# motor_drive.net
KiCad netlist of a schematic drawn in Altium Designer
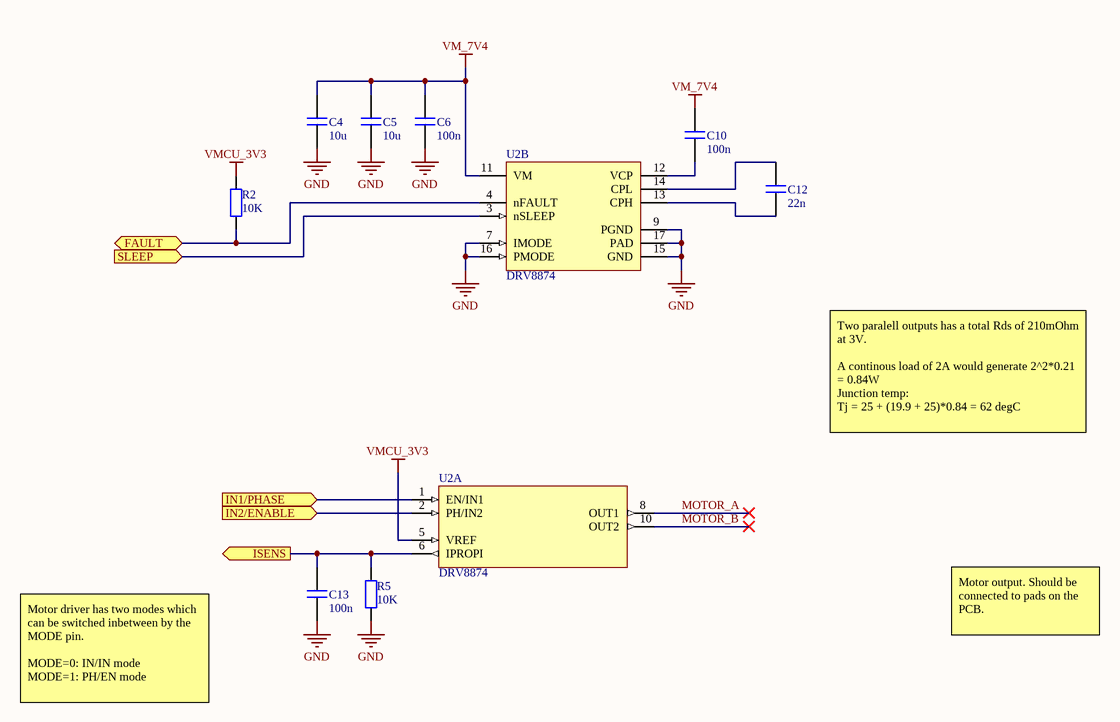
[diagram p0: motor_drive.SchDoc]

(export (version "E")
  (design (tool "Eeschema 10.0.6"))
  (components
    (comp (ref "C4")
      (value "10u")
      (footprint "CAPC3216X14N")
      (description "Capacitor")
      (fields (field (name "Comment") "cap"))
      (libsource (lib "lib_passives") (part "cap"))
    )
    (comp (ref "C5")
      (value "10u")
      (footprint "CAPC3216X14N")
      (description "Capacitor")
      (fields (field (name "Comment") "cap"))
      (libsource (lib "lib_passives") (part "cap"))
    )
    (comp (ref "C6")
      (value "100n")
      (footprint "CAPC1005X06N")
      (description "Capacitor")
      (fields (field (name "Comment") "cap"))
      (libsource (lib "lib_passives") (part "cap"))
    )
    (comp (ref "C10")
      (value "100n")
      (footprint "CAPC1005X06N")
      (description "Capacitor")
      (fields (field (name "Comment") "cap"))
      (libsource (lib "lib_passives") (part "cap"))
    )
    (comp (ref "C12")
      (value "22n")
      (footprint "CAPC1005X06N")
      (description "Capacitor")
      (fields (field (name "Comment") "cap"))
      (libsource (lib "lib_passives") (part "cap"))
    )
    (comp (ref "C13")
      (value "100n")
      (footprint "CAPC1005X06N")
      (description "Capacitor")
      (fields (field (name "Comment") "cap"))
      (libsource (lib "lib_passives") (part "cap"))
    )
    (comp (ref "R2")
      (value "10K")
      (footprint "RESC1005X04N")
      (description "Resistor")
      (fields (field (name "Comment") "res"))
      (libsource (lib "lib_passives") (part "res"))
    )
    (comp (ref "R5")
      (value "10K")
      (footprint "RESC1005X04N")
      (description "Resistor")
      (fields (field (name "Comment") "res"))
      (libsource (lib "lib_passives") (part "res"))
    )
    (comp (ref "U2")
      (value "DRV8874")
      (footprint "TSOP65P640X120_HS-17N_DRV8874")
      (description "H-Bridge Motor Driver With Integrated Current Sense and Regulation")
      (libsource (lib "lib_ti") (part "drv8874"))
    )
  )
  (nets
    (net (code "1") (name "/FAULT") (class "Default")
      (node (ref "R2") (pin "1") (pinfunction "1_1") (pintype "passive"))
      (node (ref "U2") (pin "4") (pinfunction "nFAULT_4") (pintype "open_collector"))
    )
    (net (code "2") (name "/IN1{slash}PHASE") (class "Default")
      (node (ref "U2") (pin "1") (pinfunction "EN/IN1_1") (pintype "input"))
    )
    (net (code "3") (name "/IN2{slash}ENABLE") (class "Default")
      (node (ref "U2") (pin "2") (pinfunction "PH/IN2_2") (pintype "input"))
    )
    (net (code "4") (name "/ISENS") (class "Default")
      (node (ref "C13") (pin "2") (pinfunction "2_2") (pintype "passive"))
      (node (ref "R5") (pin "2") (pinfunction "2_2") (pintype "passive"))
      (node (ref "U2") (pin "6") (pinfunction "IPROPI_6") (pintype "output"))
    )
    (net (code "5") (name "/MOTOR_A") (class "Default")
      (node (ref "U2") (pin "8") (pinfunction "OUT1_8") (pintype "output+no_connect"))
    )
    (net (code "6") (name "/MOTOR_B") (class "Default")
      (node (ref "U2") (pin "10") (pinfunction "OUT2_10") (pintype "output+no_connect"))
    )
    (net (code "7") (name "/SLEEP") (class "Default")
      (node (ref "U2") (pin "3") (pinfunction "nSLEEP_3") (pintype "input"))
    )
    (net (code "8") (name "GND") (class "Default")
      (node (ref "C13") (pin "1") (pinfunction "1_1") (pintype "passive"))
      (node (ref "C4") (pin "1") (pinfunction "1_1") (pintype "passive"))
      (node (ref "C5") (pin "1") (pinfunction "1_1") (pintype "passive"))
      (node (ref "C6") (pin "1") (pinfunction "1_1") (pintype "passive"))
      (node (ref "R5") (pin "1") (pinfunction "1_1") (pintype "passive"))
      (node (ref "U2") (pin "15") (pinfunction "GND_15") (pintype "power_in"))
      (node (ref "U2") (pin "16") (pinfunction "PMODE_16") (pintype "input"))
      (node (ref "U2") (pin "17") (pinfunction "PAD_17") (pintype "power_in"))
      (node (ref "U2") (pin "7") (pinfunction "IMODE_7") (pintype "input"))
      (node (ref "U2") (pin "9") (pinfunction "PGND_9") (pintype "power_in"))
    )
    (net (code "9") (name "Net-(U2B-CPH)") (class "Default")
      (node (ref "C12") (pin "1") (pinfunction "1_1") (pintype "passive"))
      (node (ref "U2") (pin "13") (pinfunction "CPH_13") (pintype "passive"))
    )
    (net (code "10") (name "Net-(U2B-CPL)") (class "Default")
      (node (ref "C12") (pin "2") (pinfunction "2_2") (pintype "passive"))
      (node (ref "U2") (pin "14") (pinfunction "CPL_14") (pintype "passive"))
    )
    (net (code "11") (name "Net-(U2B-VCP)") (class "Default")
      (node (ref "C10") (pin "1") (pinfunction "1_1") (pintype "passive"))
      (node (ref "U2") (pin "12") (pinfunction "VCP_12") (pintype "power_in"))
    )
    (net (code "12") (name "VMCU_3V3") (class "Default")
      (node (ref "R2") (pin "2") (pinfunction "2_2") (pintype "passive"))
      (node (ref "U2") (pin "5") (pinfunction "VREF_5") (pintype "input"))
    )
    (net (code "13") (name "VM_7V4") (class "Default")
      (node (ref "C10") (pin "2") (pinfunction "2_2") (pintype "passive"))
      (node (ref "C4") (pin "2") (pinfunction "2_2") (pintype "passive"))
      (node (ref "C5") (pin "2") (pinfunction "2_2") (pintype "passive"))
      (node (ref "C6") (pin "2") (pinfunction "2_2") (pintype "passive"))
      (node (ref "U2") (pin "11") (pinfunction "VM_11") (pintype "power_in"))
    )
  )
)
